# RelayTest.net
KiCad netlist of a schematic drawn in EAGLE
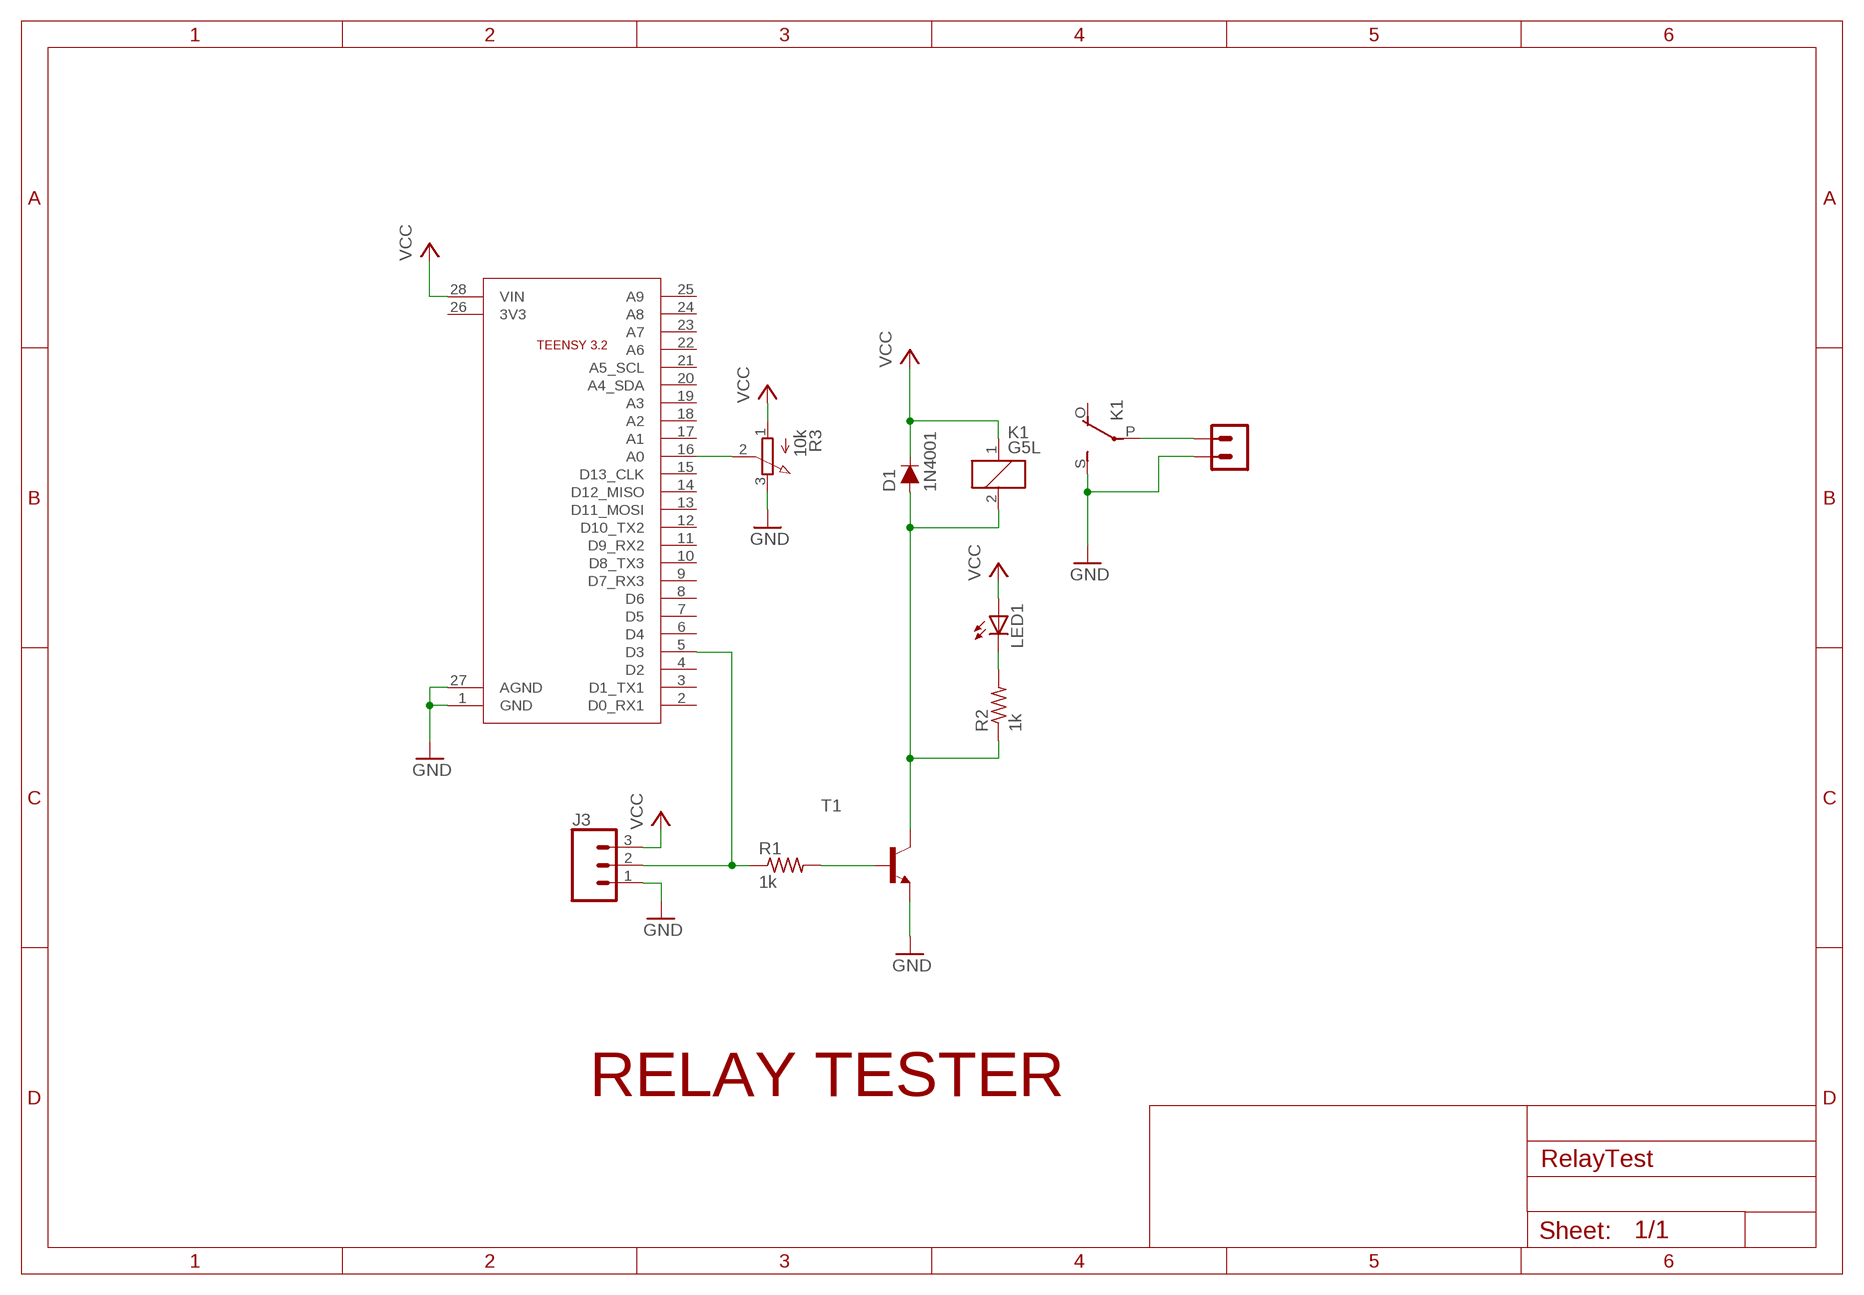
[diagram p0: schematic, sheet 1]

(export (version "E")
  (design (tool "Eeschema 10.0.6"))
  (components
    (comp (ref "D1")
      (value "1N4001")
      (footprint "eagle-import:DIODE-1N4001-KIT")
      (libsource (lib "eagle-import") (part "DIODE-KIT2"))
    )
    (comp (ref "J3")
      (value "CONN_03SCREW")
      (footprint "eagle-import:SCREWTERMINAL-3.5MM-3")
      (libsource (lib "eagle-import") (part "CONN_03SCREW"))
    )
    (comp (ref "K1")
      (value "G5L")
      (footprint "eagle-import:G5LE")
      (libsource (lib "eagle-import") (part "G5L"))
    )
    (comp (ref "LED1")
      (value "LED3MM")
      (footprint "eagle-import:LED3MM")
      (libsource (lib "eagle-import") (part "LED3MM"))
    )
    (comp (ref "R1")
      (value "1k")
      (footprint "eagle-import:0204_7")
      (libsource (lib "eagle-import") (part "R-US_0204/7"))
    )
    (comp (ref "R2")
      (value "1k")
      (footprint "eagle-import:0204_7")
      (libsource (lib "eagle-import") (part "R-US_0204/7"))
    )
    (comp (ref "R3")
      (value "10k")
      (footprint "eagle-import:3RP_1610N")
      (libsource (lib "eagle-import") (part "3RP/1610N"))
    )
    (comp (ref "T1")
      (value "-NPN-TO92-EBC")
      (footprint "eagle-import:TO92-EBC")
      (libsource (lib "eagle-import") (part "-NPN-TO92-EBC"))
    )
    (comp (ref "U$1")
      (value "TEENSY3.2")
      (footprint "eagle-import:TEENSY")
      (libsource (lib "eagle-import") (part "TEENSY3.2"))
    )
    (comp (ref "U$2")
      (value "BIG_TERMINAL_2PINBIG")
      (footprint "eagle-import:BIG_TERMINAL_2PIN")
      (libsource (lib "eagle-import") (part "BIG_TERMINAL_2PINBIG"))
    )
  )
  (nets
    (net (code "1") (name "GND") (class "Default")
      (node (ref "J3") (pin "1") (pinfunction "1_1") (pintype "passive"))
      (node (ref "K1") (pin "S") (pinfunction "S_S") (pintype "passive"))
      (node (ref "R3") (pin "3") (pinfunction "E_3") (pintype "passive"))
      (node (ref "T1") (pin "E") (pinfunction "E_E") (pintype "passive"))
      (node (ref "U$1") (pin "1") (pinfunction "GND_1") (pintype "bidirectional"))
      (node (ref "U$1") (pin "27") (pinfunction "AGND_27") (pintype "bidirectional"))
      (node (ref "U$2") (pin "P$2") (pinfunction "P$2_P$2") (pintype "bidirectional"))
    )
    (net (code "2") (name "Net-(D1-PadA)") (class "Default")
      (node (ref "D1") (pin "A") (pinfunction "A_A") (pintype "passive"))
      (node (ref "K1") (pin "2") (pinfunction "2_2") (pintype "passive"))
      (node (ref "R2") (pin "1") (pinfunction "1_1") (pintype "passive"))
      (node (ref "T1") (pin "C") (pinfunction "C_C") (pintype "passive"))
    )
    (net (code "3") (name "Net-(K1-PadP)") (class "Default")
      (node (ref "K1") (pin "P") (pinfunction "P_P") (pintype "passive"))
      (node (ref "U$2") (pin "P$1") (pinfunction "P$1_P$1") (pintype "bidirectional"))
    )
    (net (code "4") (name "Net-(LED1-C)") (class "Default")
      (node (ref "LED1") (pin "K") (pinfunction "C_K") (pintype "passive"))
      (node (ref "R2") (pin "2") (pinfunction "2_2") (pintype "passive"))
    )
    (net (code "5") (name "Net-(R1-Pad2)") (class "Default")
      (node (ref "R1") (pin "2") (pinfunction "2_2") (pintype "passive"))
      (node (ref "T1") (pin "B") (pinfunction "B_B") (pintype "passive"))
    )
    (net (code "6") (name "Net-(R3-S)") (class "Default")
      (node (ref "R3") (pin "2") (pinfunction "S_2") (pintype "passive"))
      (node (ref "U$1") (pin "16") (pinfunction "A0_16") (pintype "bidirectional"))
    )
    (net (code "7") (name "Net-(U$1-D3)") (class "Default")
      (node (ref "J3") (pin "2") (pinfunction "2_2") (pintype "passive"))
      (node (ref "R1") (pin "1") (pinfunction "1_1") (pintype "passive"))
      (node (ref "U$1") (pin "5") (pinfunction "D3_5") (pintype "bidirectional"))
    )
    (net (code "8") (name "VCC") (class "Default")
      (node (ref "D1") (pin "C") (pinfunction "C_C") (pintype "passive"))
      (node (ref "J3") (pin "3") (pinfunction "3_3") (pintype "passive"))
      (node (ref "K1") (pin "1") (pinfunction "1_1") (pintype "passive"))
      (node (ref "LED1") (pin "A") (pinfunction "A_A") (pintype "passive"))
      (node (ref "R3") (pin "1") (pinfunction "A_1") (pintype "passive"))
      (node (ref "U$1") (pin "28") (pinfunction "VIN_28") (pintype "bidirectional"))
    )
    (net (code "9") (name "unconnected-(K1-PadO)") (class "Default")
      (node (ref "K1") (pin "O") (pinfunction "O_O") (pintype "passive"))
    )
    (net (code "10") (name "unconnected-(U$1-3V3-Pad26)") (class "Default")
      (node (ref "U$1") (pin "26") (pinfunction "3V3_26") (pintype "bidirectional"))
    )
    (net (code "11") (name "unconnected-(U$1-A1-Pad17)") (class "Default")
      (node (ref "U$1") (pin "17") (pinfunction "A1_17") (pintype "bidirectional"))
    )
    (net (code "12") (name "unconnected-(U$1-A2-Pad18)") (class "Default")
      (node (ref "U$1") (pin "18") (pinfunction "A2_18") (pintype "bidirectional"))
    )
    (net (code "13") (name "unconnected-(U$1-A3-Pad19)") (class "Default")
      (node (ref "U$1") (pin "19") (pinfunction "A3_19") (pintype "bidirectional"))
    )
    (net (code "14") (name "unconnected-(U$1-A4_SDA-Pad20)") (class "Default")
      (node (ref "U$1") (pin "20") (pinfunction "A4_SDA_20") (pintype "bidirectional"))
    )
    (net (code "15") (name "unconnected-(U$1-A5_SCL-Pad21)") (class "Default")
      (node (ref "U$1") (pin "21") (pinfunction "A5_SCL_21") (pintype "bidirectional"))
    )
    (net (code "16") (name "unconnected-(U$1-A6-Pad22)") (class "Default")
      (node (ref "U$1") (pin "22") (pinfunction "A6_22") (pintype "bidirectional"))
    )
    (net (code "17") (name "unconnected-(U$1-A7-Pad23)") (class "Default")
      (node (ref "U$1") (pin "23") (pinfunction "A7_23") (pintype "bidirectional"))
    )
    (net (code "18") (name "unconnected-(U$1-A8-Pad24)") (class "Default")
      (node (ref "U$1") (pin "24") (pinfunction "A8_24") (pintype "bidirectional"))
    )
    (net (code "19") (name "unconnected-(U$1-A9-Pad25)") (class "Default")
      (node (ref "U$1") (pin "25") (pinfunction "A9_25") (pintype "bidirectional"))
    )
    (net (code "20") (name "unconnected-(U$1-D0_RX1-Pad2)") (class "Default")
      (node (ref "U$1") (pin "2") (pinfunction "D0_RX1_2") (pintype "bidirectional"))
    )
    (net (code "21") (name "unconnected-(U$1-D1_TX1-Pad3)") (class "Default")
      (node (ref "U$1") (pin "3") (pinfunction "D1_TX1_3") (pintype "bidirectional"))
    )
    (net (code "22") (name "unconnected-(U$1-D2-Pad4)") (class "Default")
      (node (ref "U$1") (pin "4") (pinfunction "D2_4") (pintype "bidirectional"))
    )
    (net (code "23") (name "unconnected-(U$1-D4-Pad6)") (class "Default")
      (node (ref "U$1") (pin "6") (pinfunction "D4_6") (pintype "bidirectional"))
    )
    (net (code "24") (name "unconnected-(U$1-D5-Pad7)") (class "Default")
      (node (ref "U$1") (pin "7") (pinfunction "D5_7") (pintype "bidirectional"))
    )
    (net (code "25") (name "unconnected-(U$1-D6-Pad8)") (class "Default")
      (node (ref "U$1") (pin "8") (pinfunction "D6_8") (pintype "bidirectional"))
    )
    (net (code "26") (name "unconnected-(U$1-D7_RX3-Pad9)") (class "Default")
      (node (ref "U$1") (pin "9") (pinfunction "D7_RX3_9") (pintype "bidirectional"))
    )
    (net (code "27") (name "unconnected-(U$1-D8_TX3-Pad10)") (class "Default")
      (node (ref "U$1") (pin "10") (pinfunction "D8_TX3_10") (pintype "bidirectional"))
    )
    (net (code "28") (name "unconnected-(U$1-D9_RX2-Pad11)") (class "Default")
      (node (ref "U$1") (pin "11") (pinfunction "D9_RX2_11") (pintype "bidirectional"))
    )
    (net (code "29") (name "unconnected-(U$1-D10_TX2-Pad12)") (class "Default")
      (node (ref "U$1") (pin "12") (pinfunction "D10_TX2_12") (pintype "bidirectional"))
    )
    (net (code "30") (name "unconnected-(U$1-D11_MOSI-Pad13)") (class "Default")
      (node (ref "U$1") (pin "13") (pinfunction "D11_MOSI_13") (pintype "bidirectional"))
    )
    (net (code "31") (name "unconnected-(U$1-D12_MISO-Pad14)") (class "Default")
      (node (ref "U$1") (pin "14") (pinfunction "D12_MISO_14") (pintype "bidirectional"))
    )
    (net (code "32") (name "unconnected-(U$1-D13_CLK-Pad15)") (class "Default")
      (node (ref "U$1") (pin "15") (pinfunction "D13_CLK_15") (pintype "bidirectional"))
    )
  )
)
